# hurf1_board.net
KiCad netlist of a schematic drawn in EAGLE
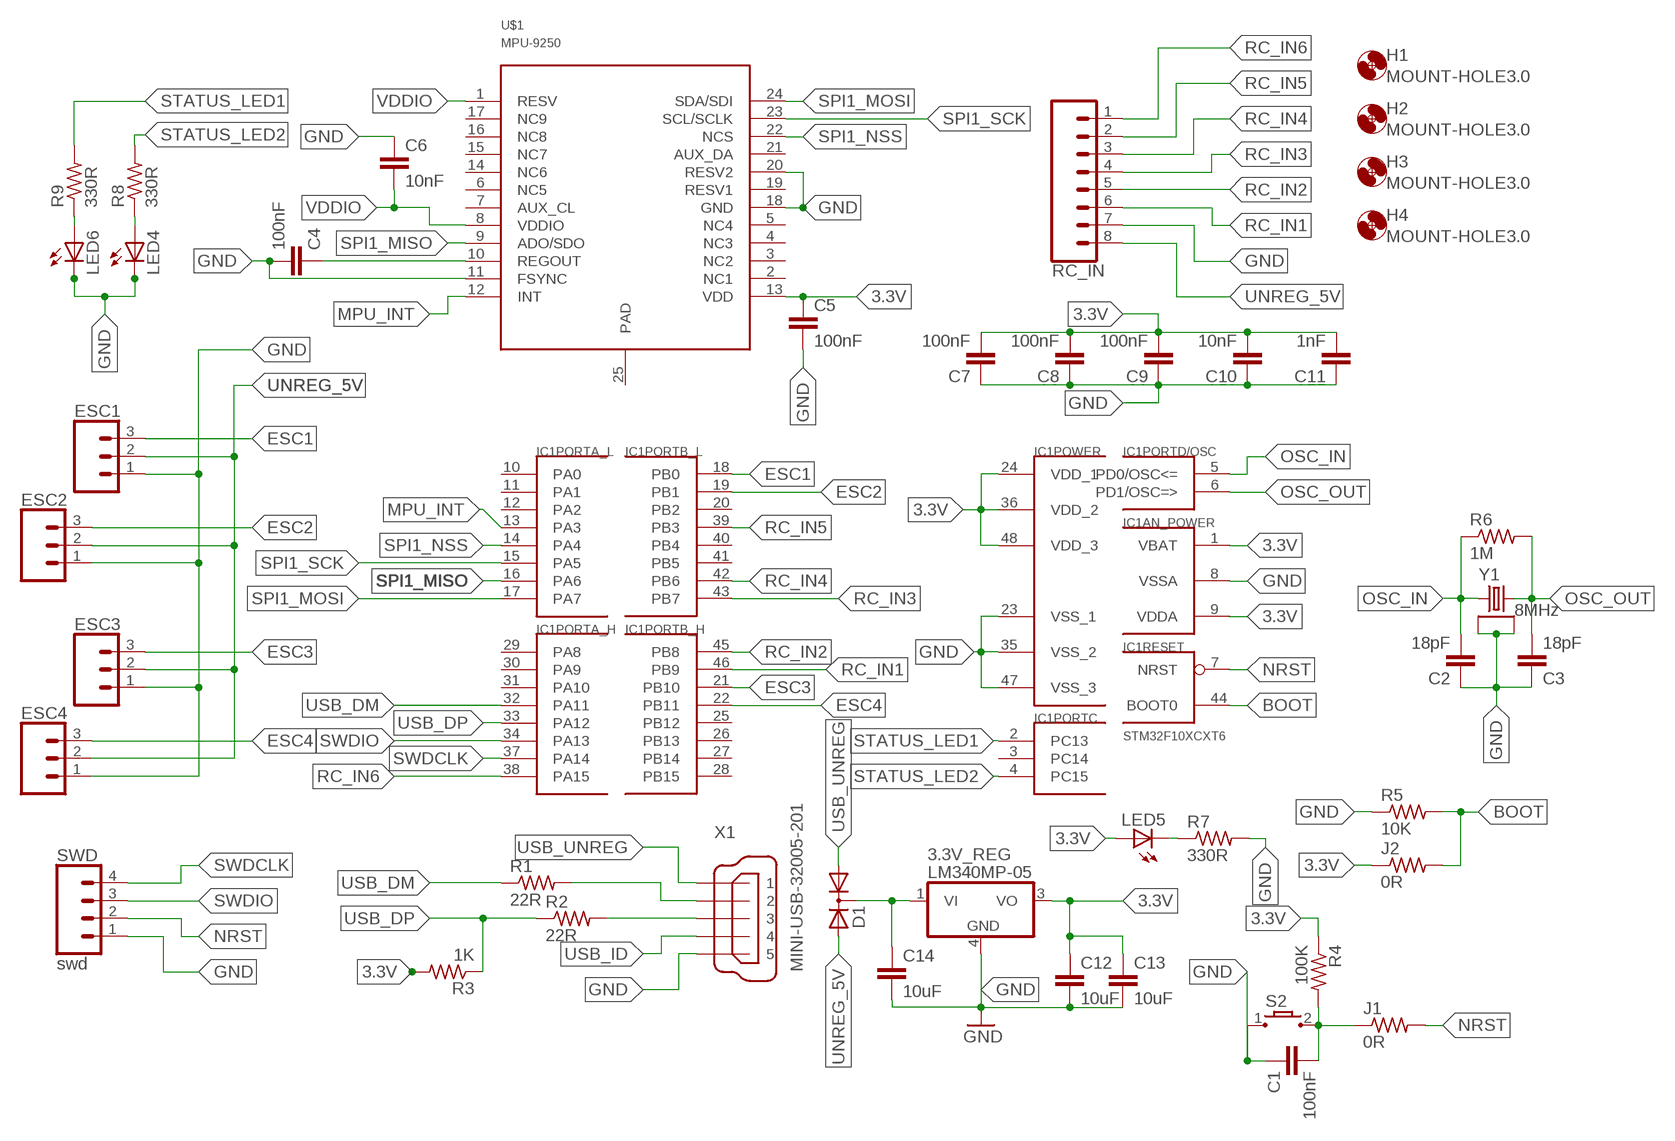
[diagram p0: schematic, sheet 1]

(export (version "E")
  (design (tool "Eeschema 10.0.6"))
  (components
    (comp (ref "3.3V_REG")
      (value "LM340MP-05")
      (footprint "eagle-import:SOT223")
      (libsource (lib "eagle-import") (part "LM340?-MP05"))
    )
    (comp (ref "C1")
      (value "100nF")
      (footprint "eagle-import:C0603")
      (libsource (lib "eagle-import") (part "C-EUC0603"))
    )
    (comp (ref "C2")
      (value "18pF")
      (footprint "eagle-import:C0603")
      (libsource (lib "eagle-import") (part "C-EUC0603"))
    )
    (comp (ref "C3")
      (value "18pF")
      (footprint "eagle-import:C0603")
      (libsource (lib "eagle-import") (part "C-EUC0603"))
    )
    (comp (ref "C4")
      (value "100nF")
      (footprint "eagle-import:C0805K")
      (libsource (lib "eagle-import") (part "resistor_348_C-EUC0805K"))
    )
    (comp (ref "C5")
      (value "100nF")
      (footprint "eagle-import:C0603")
      (libsource (lib "eagle-import") (part "C-EUC0603"))
    )
    (comp (ref "C6")
      (value "10nF")
      (footprint "eagle-import:C0603")
      (libsource (lib "eagle-import") (part "C-EUC0603"))
    )
    (comp (ref "C7")
      (value "100nF")
      (footprint "eagle-import:C0603")
      (libsource (lib "eagle-import") (part "C-EUC0603"))
    )
    (comp (ref "C8")
      (value "100nF")
      (footprint "eagle-import:C0603")
      (libsource (lib "eagle-import") (part "C-EUC0603"))
    )
    (comp (ref "C9")
      (value "100nF")
      (footprint "eagle-import:C0603")
      (libsource (lib "eagle-import") (part "C-EUC0603"))
    )
    (comp (ref "C10")
      (value "10nF")
      (footprint "eagle-import:C0603")
      (libsource (lib "eagle-import") (part "C-EUC0603"))
    )
    (comp (ref "C11")
      (value "1nF")
      (footprint "eagle-import:C0603")
      (libsource (lib "eagle-import") (part "C-EUC0603"))
    )
    (comp (ref "C12")
      (value "10uF")
      (footprint "eagle-import:C0805")
      (libsource (lib "eagle-import") (part "C-EUC0805"))
    )
    (comp (ref "C13")
      (value "10uF")
      (footprint "eagle-import:C0805")
      (libsource (lib "eagle-import") (part "C-EUC0805"))
    )
    (comp (ref "C14")
      (value "10uF")
      (footprint "eagle-import:C0805")
      (libsource (lib "eagle-import") (part "C-EUC0805"))
    )
    (comp (ref "D1")
      (value "DIODE-2AC|CASOT23")
      (footprint "eagle-import:SOT23")
      (libsource (lib "eagle-import") (part "DIODE-2AC|CASOT23"))
    )
    (comp (ref "ESC1")
      (value "CONN_03")
      (footprint "eagle-import:1X03")
      (libsource (lib "eagle-import") (part "CONN_03"))
    )
    (comp (ref "ESC2")
      (value "CONN_03")
      (footprint "eagle-import:1X03")
      (libsource (lib "eagle-import") (part "CONN_03"))
    )
    (comp (ref "ESC3")
      (value "CONN_03")
      (footprint "eagle-import:1X03")
      (libsource (lib "eagle-import") (part "CONN_03"))
    )
    (comp (ref "ESC4")
      (value "CONN_03")
      (footprint "eagle-import:1X03")
      (libsource (lib "eagle-import") (part "CONN_03"))
    )
    (comp (ref "H1")
      (value "MOUNT-HOLE3.0")
      (footprint "eagle-import:3,0")
      (libsource (lib "eagle-import") (part "MOUNT-HOLE3.0"))
    )
    (comp (ref "H2")
      (value "MOUNT-HOLE3.0")
      (footprint "eagle-import:3,0")
      (libsource (lib "eagle-import") (part "MOUNT-HOLE3.0"))
    )
    (comp (ref "H3")
      (value "MOUNT-HOLE3.0")
      (footprint "eagle-import:3,0")
      (libsource (lib "eagle-import") (part "MOUNT-HOLE3.0"))
    )
    (comp (ref "H4")
      (value "MOUNT-HOLE3.0")
      (footprint "eagle-import:3,0")
      (libsource (lib "eagle-import") (part "MOUNT-HOLE3.0"))
    )
    (comp (ref "IC1")
      (value "STM32F10XCXT6")
      (footprint "eagle-import:TQFP48")
      (libsource (lib "eagle-import") (part "STM32F10XCXT6"))
    )
    (comp (ref "J1")
      (value "0R")
      (footprint "eagle-import:R0603")
      (libsource (lib "eagle-import") (part "R-US_R0603"))
    )
    (comp (ref "J2")
      (value "0R")
      (footprint "eagle-import:R0603")
      (libsource (lib "eagle-import") (part "R-US_R0603"))
    )
    (comp (ref "LED4")
      (value "LEDSML0805")
      (footprint "eagle-import:SML0805")
      (libsource (lib "eagle-import") (part "LEDSML0805"))
    )
    (comp (ref "LED5")
      (value "LEDSML0805")
      (footprint "eagle-import:SML0805")
      (libsource (lib "eagle-import") (part "LEDSML0805"))
    )
    (comp (ref "LED6")
      (value "LEDSML0805")
      (footprint "eagle-import:SML0805")
      (libsource (lib "eagle-import") (part "LEDSML0805"))
    )
    (comp (ref "R1")
      (value "22R")
      (footprint "eagle-import:R0603")
      (libsource (lib "eagle-import") (part "R-US_R0603"))
    )
    (comp (ref "R2")
      (value "22R")
      (footprint "eagle-import:R0603")
      (libsource (lib "eagle-import") (part "R-US_R0603"))
    )
    (comp (ref "R3")
      (value "1K")
      (footprint "eagle-import:R0603")
      (libsource (lib "eagle-import") (part "R-US_R0603"))
    )
    (comp (ref "R4")
      (value "100K")
      (footprint "eagle-import:R0603")
      (libsource (lib "eagle-import") (part "R-US_R0603"))
    )
    (comp (ref "R5")
      (value "10K")
      (footprint "eagle-import:R0603")
      (libsource (lib "eagle-import") (part "R-US_R0603"))
    )
    (comp (ref "R6")
      (value "1M")
      (footprint "eagle-import:R0603")
      (libsource (lib "eagle-import") (part "R-US_R0603"))
    )
    (comp (ref "R7")
      (value "330R")
      (footprint "eagle-import:R0603")
      (libsource (lib "eagle-import") (part "R-US_R0603"))
    )
    (comp (ref "R8")
      (value "330R")
      (footprint "eagle-import:R0603")
      (libsource (lib "eagle-import") (part "R-US_R0603"))
    )
    (comp (ref "R9")
      (value "330R")
      (footprint "eagle-import:R0603")
      (libsource (lib "eagle-import") (part "R-US_R0603"))
    )
    (comp (ref "RC_IN")
      (value "CONN_08")
      (footprint "eagle-import:1X08_1MM_RA")
      (libsource (lib "eagle-import") (part "CONN_08"))
    )
    (comp (ref "S2")
      (value "TL3302-G")
      (footprint "eagle-import:TL3302_GULL_WING")
      (libsource (lib "eagle-import") (part "TL3302-G"))
    )
    (comp (ref "SWD")
      (value "swd")
      (footprint "eagle-import:1X04_1MM_RA")
      (libsource (lib "eagle-import") (part "CONN_04SMD2"))
    )
    (comp (ref "U$1")
      (value "MPU-9250")
      (footprint "eagle-import:LEAD-QFN24")
      (libsource (lib "eagle-import") (part "MPU-9250"))
    )
    (comp (ref "X1")
      (value "MINI-USB-32005-201")
      (footprint "eagle-import:32005-201")
      (libsource (lib "eagle-import") (part "MINI-USB-32005-201"))
    )
    (comp (ref "Y1")
      (value "8MHz")
      (footprint "eagle-import:GSX-531")
      (libsource (lib "eagle-import") (part "GSX-531"))
    )
  )
  (nets
    (net (code "1") (name "3.3V") (class "Default")
      (node (ref "3.3V_REG") (pin "3") (pinfunction "VO_3") (pintype "passive"))
      (node (ref "C10") (pin "2") (pinfunction "2_2") (pintype "passive"))
      (node (ref "C11") (pin "2") (pinfunction "2_2") (pintype "passive"))
      (node (ref "C12") (pin "1") (pinfunction "1_1") (pintype "passive"))
      (node (ref "C13") (pin "1") (pinfunction "1_1") (pintype "passive"))
      (node (ref "C5") (pin "1") (pinfunction "1_1") (pintype "passive"))
      (node (ref "C7") (pin "2") (pinfunction "2_2") (pintype "passive"))
      (node (ref "C8") (pin "2") (pinfunction "2_2") (pintype "passive"))
      (node (ref "C9") (pin "2") (pinfunction "2_2") (pintype "passive"))
      (node (ref "IC1") (pin "1") (pinfunction "VBAT_1") (pintype "power_in"))
      (node (ref "IC1") (pin "24") (pinfunction "VDD_1_24") (pintype "power_in"))
      (node (ref "IC1") (pin "36") (pinfunction "VDD_2_36") (pintype "power_in"))
      (node (ref "IC1") (pin "48") (pinfunction "VDD_3_48") (pintype "power_in"))
      (node (ref "IC1") (pin "9") (pinfunction "VDDA_9") (pintype "power_in"))
      (node (ref "J2") (pin "1") (pinfunction "1_1") (pintype "passive"))
      (node (ref "LED5") (pin "A") (pinfunction "A_A") (pintype "passive"))
      (node (ref "R3") (pin "2") (pinfunction "2_2") (pintype "passive"))
      (node (ref "R4") (pin "1") (pinfunction "1_1") (pintype "passive"))
      (node (ref "U$1") (pin "13") (pinfunction "VDD_13") (pintype "bidirectional"))
    )
    (net (code "2") (name "BOOT") (class "Default")
      (node (ref "IC1") (pin "44") (pinfunction "BOOT0_44") (pintype "input"))
      (node (ref "J2") (pin "2") (pinfunction "2_2") (pintype "passive"))
      (node (ref "R5") (pin "2") (pinfunction "2_2") (pintype "passive"))
    )
    (net (code "3") (name "ESC1") (class "Default")
      (node (ref "ESC1") (pin "3") (pinfunction "3_3") (pintype "passive"))
      (node (ref "IC1") (pin "18") (pinfunction "PB0_18") (pintype "bidirectional"))
    )
    (net (code "4") (name "ESC2") (class "Default")
      (node (ref "ESC2") (pin "3") (pinfunction "3_3") (pintype "passive"))
      (node (ref "IC1") (pin "19") (pinfunction "PB1_19") (pintype "bidirectional"))
    )
    (net (code "5") (name "ESC3") (class "Default")
      (node (ref "ESC3") (pin "3") (pinfunction "3_3") (pintype "passive"))
      (node (ref "IC1") (pin "21") (pinfunction "PB10_21") (pintype "bidirectional"))
    )
    (net (code "6") (name "ESC4") (class "Default")
      (node (ref "ESC4") (pin "3") (pinfunction "3_3") (pintype "passive"))
      (node (ref "IC1") (pin "22") (pinfunction "PB11_22") (pintype "bidirectional"))
    )
    (net (code "7") (name "GND") (class "Default")
      (node (ref "3.3V_REG") (pin "4") (pinfunction "GND_4") (pintype "passive"))
      (node (ref "C1") (pin "1") (pinfunction "1_1") (pintype "passive"))
      (node (ref "C10") (pin "1") (pinfunction "1_1") (pintype "passive"))
      (node (ref "C11") (pin "1") (pinfunction "1_1") (pintype "passive"))
      (node (ref "C12") (pin "2") (pinfunction "2_2") (pintype "passive"))
      (node (ref "C13") (pin "2") (pinfunction "2_2") (pintype "passive"))
      (node (ref "C14") (pin "2") (pinfunction "2_2") (pintype "passive"))
      (node (ref "C2") (pin "1") (pinfunction "1_1") (pintype "passive"))
      (node (ref "C3") (pin "1") (pinfunction "1_1") (pintype "passive"))
      (node (ref "C4") (pin "2") (pinfunction "2_2") (pintype "passive"))
      (node (ref "C5") (pin "2") (pinfunction "2_2") (pintype "passive"))
      (node (ref "C6") (pin "1") (pinfunction "1_1") (pintype "passive"))
      (node (ref "C7") (pin "1") (pinfunction "1_1") (pintype "passive"))
      (node (ref "C8") (pin "1") (pinfunction "1_1") (pintype "passive"))
      (node (ref "C9") (pin "1") (pinfunction "1_1") (pintype "passive"))
      (node (ref "ESC1") (pin "1") (pinfunction "1_1") (pintype "passive"))
      (node (ref "ESC2") (pin "1") (pinfunction "1_1") (pintype "passive"))
      (node (ref "ESC3") (pin "1") (pinfunction "1_1") (pintype "passive"))
      (node (ref "ESC4") (pin "1") (pinfunction "1_1") (pintype "passive"))
      (node (ref "IC1") (pin "23") (pinfunction "VSS_1_23") (pintype "power_in"))
      (node (ref "IC1") (pin "35") (pinfunction "VSS_2_35") (pintype "power_in"))
      (node (ref "IC1") (pin "47") (pinfunction "VSS_3_47") (pintype "power_in"))
      (node (ref "IC1") (pin "8") (pinfunction "VSSA_8") (pintype "power_in"))
      (node (ref "LED4") (pin "C") (pinfunction "C_C") (pintype "passive"))
      (node (ref "LED6") (pin "C") (pinfunction "C_C") (pintype "passive"))
      (node (ref "R5") (pin "1") (pinfunction "1_1") (pintype "passive"))
      (node (ref "R7") (pin "2") (pinfunction "2_2") (pintype "passive"))
      (node (ref "RC_IN") (pin "7") (pinfunction "7_7") (pintype "passive"))
      (node (ref "S2") (pin "1") (pinfunction "1_1") (pintype "passive"))
      (node (ref "SWD") (pin "1") (pinfunction "1_1") (pintype "passive"))
      (node (ref "U$1") (pin "11") (pinfunction "FSYNC_11") (pintype "bidirectional"))
      (node (ref "U$1") (pin "18") (pinfunction "GND_18") (pintype "bidirectional"))
      (node (ref "U$1") (pin "20") (pinfunction "RESV2_20") (pintype "bidirectional"))
      (node (ref "X1") (pin "5") (pinfunction "5_5") (pintype "passive"))
      (node (ref "Y1") (pin "2") (pinfunction "2_2") (pintype "passive"))
      (node (ref "Y1") (pin "4") (pinfunction "4_4") (pintype "passive"))
    )
    (net (code "8") (name "MPU_INT") (class "Default")
      (node (ref "IC1") (pin "13") (pinfunction "PA3_13") (pintype "bidirectional"))
      (node (ref "U$1") (pin "12") (pinfunction "INT_12") (pintype "bidirectional"))
    )
    (net (code "9") (name "NRST") (class "Default")
      (node (ref "IC1") (pin "7") (pinfunction "NRST_7") (pintype "input"))
      (node (ref "J1") (pin "2") (pinfunction "2_2") (pintype "passive"))
      (node (ref "SWD") (pin "2") (pinfunction "2_2") (pintype "passive"))
    )
    (net (code "10") (name "Net-(3.3V_REG-VI)") (class "Default")
      (node (ref "3.3V_REG") (pin "1") (pinfunction "VI_1") (pintype "input"))
      (node (ref "C14") (pin "1") (pinfunction "1_1") (pintype "passive"))
      (node (ref "D1") (pin "3") (pinfunction "C_3") (pintype "passive"))
    )
    (net (code "11") (name "Net-(C1-Pad2)") (class "Default")
      (node (ref "C1") (pin "2") (pinfunction "2_2") (pintype "passive"))
      (node (ref "J1") (pin "1") (pinfunction "1_1") (pintype "passive"))
      (node (ref "R4") (pin "2") (pinfunction "2_2") (pintype "passive"))
      (node (ref "S2") (pin "2") (pinfunction "2_2") (pintype "passive"))
    )
    (net (code "12") (name "Net-(LED4-PadA)") (class "Default")
      (node (ref "LED4") (pin "A") (pinfunction "A_A") (pintype "passive"))
      (node (ref "R8") (pin "1") (pinfunction "1_1") (pintype "passive"))
    )
    (net (code "13") (name "Net-(LED5-PadC)") (class "Default")
      (node (ref "LED5") (pin "C") (pinfunction "C_C") (pintype "passive"))
      (node (ref "R7") (pin "1") (pinfunction "1_1") (pintype "passive"))
    )
    (net (code "14") (name "Net-(LED6-PadA)") (class "Default")
      (node (ref "LED6") (pin "A") (pinfunction "A_A") (pintype "passive"))
      (node (ref "R9") (pin "1") (pinfunction "1_1") (pintype "passive"))
    )
    (net (code "15") (name "Net-(R1-Pad2)") (class "Default")
      (node (ref "R1") (pin "2") (pinfunction "2_2") (pintype "passive"))
      (node (ref "X1") (pin "2") (pinfunction "2_2") (pintype "passive"))
    )
    (net (code "16") (name "Net-(R2-Pad2)") (class "Default")
      (node (ref "R2") (pin "2") (pinfunction "2_2") (pintype "passive"))
      (node (ref "X1") (pin "3") (pinfunction "3_3") (pintype "passive"))
    )
    (net (code "17") (name "Net-(U$1-REGOUT)") (class "Default")
      (node (ref "C4") (pin "1") (pinfunction "1_1") (pintype "passive"))
      (node (ref "U$1") (pin "10") (pinfunction "REGOUT_10") (pintype "bidirectional"))
    )
    (net (code "18") (name "OSC_IN") (class "Default")
      (node (ref "C2") (pin "2") (pinfunction "2_2") (pintype "passive"))
      (node (ref "IC1") (pin "5") (pinfunction "PD0/OSC<=_5") (pintype "bidirectional"))
      (node (ref "R6") (pin "1") (pinfunction "1_1") (pintype "passive"))
      (node (ref "Y1") (pin "1") (pinfunction "1_1") (pintype "passive"))
    )
    (net (code "19") (name "OSC_OUT") (class "Default")
      (node (ref "C3") (pin "2") (pinfunction "2_2") (pintype "passive"))
      (node (ref "IC1") (pin "6") (pinfunction "PD1/OSC=>_6") (pintype "bidirectional"))
      (node (ref "R6") (pin "2") (pinfunction "2_2") (pintype "passive"))
      (node (ref "Y1") (pin "3") (pinfunction "3_3") (pintype "passive"))
    )
    (net (code "20") (name "RC_IN1") (class "Default")
      (node (ref "IC1") (pin "46") (pinfunction "PB9_46") (pintype "bidirectional"))
      (node (ref "RC_IN") (pin "6") (pinfunction "6_6") (pintype "passive"))
    )
    (net (code "21") (name "RC_IN2") (class "Default")
      (node (ref "IC1") (pin "45") (pinfunction "PB8_45") (pintype "bidirectional"))
      (node (ref "RC_IN") (pin "5") (pinfunction "5_5") (pintype "passive"))
    )
    (net (code "22") (name "RC_IN3") (class "Default")
      (node (ref "IC1") (pin "43") (pinfunction "PB7_43") (pintype "bidirectional"))
      (node (ref "RC_IN") (pin "4") (pinfunction "4_4") (pintype "passive"))
    )
    (net (code "23") (name "RC_IN4") (class "Default")
      (node (ref "IC1") (pin "42") (pinfunction "PB6_42") (pintype "bidirectional"))
      (node (ref "RC_IN") (pin "3") (pinfunction "3_3") (pintype "passive"))
    )
    (net (code "24") (name "RC_IN5") (class "Default")
      (node (ref "IC1") (pin "39") (pinfunction "PB3_39") (pintype "bidirectional"))
      (node (ref "RC_IN") (pin "2") (pinfunction "2_2") (pintype "passive"))
    )
    (net (code "25") (name "RC_IN6") (class "Default")
      (node (ref "IC1") (pin "38") (pinfunction "PA15_38") (pintype "bidirectional"))
      (node (ref "RC_IN") (pin "1") (pinfunction "1_1") (pintype "passive"))
    )
    (net (code "26") (name "SPI1_MISO") (class "Default")
      (node (ref "IC1") (pin "16") (pinfunction "PA6_16") (pintype "bidirectional"))
      (node (ref "U$1") (pin "9") (pinfunction "ADO/SDO_9") (pintype "bidirectional"))
    )
    (net (code "27") (name "SPI1_MOSI") (class "Default")
      (node (ref "IC1") (pin "17") (pinfunction "PA7_17") (pintype "bidirectional"))
      (node (ref "U$1") (pin "24") (pinfunction "SDA/SDI_24") (pintype "bidirectional"))
    )
    (net (code "28") (name "SPI1_NSS") (class "Default")
      (node (ref "IC1") (pin "14") (pinfunction "PA4_14") (pintype "bidirectional"))
      (node (ref "U$1") (pin "22") (pinfunction "NCS_22") (pintype "bidirectional"))
    )
    (net (code "29") (name "SPI1_SCK") (class "Default")
      (node (ref "IC1") (pin "15") (pinfunction "PA5_15") (pintype "bidirectional"))
      (node (ref "U$1") (pin "23") (pinfunction "SCL/SCLK_23") (pintype "bidirectional"))
    )
    (net (code "30") (name "STATUS_LED1") (class "Default")
      (node (ref "IC1") (pin "2") (pinfunction "PC13_2") (pintype "bidirectional"))
      (node (ref "R9") (pin "2") (pinfunction "2_2") (pintype "passive"))
    )
    (net (code "31") (name "STATUS_LED2") (class "Default")
      (node (ref "IC1") (pin "4") (pinfunction "PC15_4") (pintype "bidirectional"))
      (node (ref "R8") (pin "2") (pinfunction "2_2") (pintype "passive"))
    )
    (net (code "32") (name "SWDCLK") (class "Default")
      (node (ref "IC1") (pin "37") (pinfunction "PA14_37") (pintype "bidirectional"))
      (node (ref "SWD") (pin "4") (pinfunction "4_4") (pintype "passive"))
    )
    (net (code "33") (name "SWDIO") (class "Default")
      (node (ref "IC1") (pin "34") (pinfunction "PA13_34") (pintype "bidirectional"))
      (node (ref "SWD") (pin "3") (pinfunction "3_3") (pintype "passive"))
    )
    (net (code "34") (name "UNREG_5V") (class "Default")
      (node (ref "D1") (pin "2") (pinfunction "A2_2") (pintype "passive"))
      (node (ref "ESC1") (pin "2") (pinfunction "2_2") (pintype "passive"))
      (node (ref "ESC2") (pin "2") (pinfunction "2_2") (pintype "passive"))
      (node (ref "ESC3") (pin "2") (pinfunction "2_2") (pintype "passive"))
      (node (ref "ESC4") (pin "2") (pinfunction "2_2") (pintype "passive"))
      (node (ref "RC_IN") (pin "8") (pinfunction "8_8") (pintype "passive"))
    )
    (net (code "35") (name "USB_DM") (class "Default")
      (node (ref "IC1") (pin "32") (pinfunction "PA11_32") (pintype "bidirectional"))
      (node (ref "R1") (pin "1") (pinfunction "1_1") (pintype "passive"))
    )
    (net (code "36") (name "USB_DP") (class "Default")
      (node (ref "IC1") (pin "33") (pinfunction "PA12_33") (pintype "bidirectional"))
      (node (ref "R2") (pin "1") (pinfunction "1_1") (pintype "passive"))
      (node (ref "R3") (pin "1") (pinfunction "1_1") (pintype "passive"))
    )
    (net (code "37") (name "USB_ID") (class "Default")
      (node (ref "X1") (pin "4") (pinfunction "4_4") (pintype "passive"))
    )
    (net (code "38") (name "USB_UNREG") (class "Default")
      (node (ref "D1") (pin "1") (pinfunction "A1_1") (pintype "passive"))
      (node (ref "X1") (pin "1") (pinfunction "1_1") (pintype "passive"))
    )
    (net (code "39") (name "VDDIO") (class "Default")
      (node (ref "C6") (pin "2") (pinfunction "2_2") (pintype "passive"))
      (node (ref "U$1") (pin "1") (pinfunction "RESV_1") (pintype "bidirectional"))
      (node (ref "U$1") (pin "8") (pinfunction "VDDIO_8") (pintype "bidirectional"))
    )
    (net (code "40") (name "unconnected-(IC1B-PA8-Pad29)") (class "Default")
      (node (ref "IC1") (pin "29") (pinfunction "PA8_29") (pintype "bidirectional"))
    )
    (net (code "41") (name "unconnected-(IC1B-PA9-Pad30)") (class "Default")
      (node (ref "IC1") (pin "30") (pinfunction "PA9_30") (pintype "bidirectional"))
    )
    (net (code "42") (name "unconnected-(IC1B-PA10-Pad31)") (class "Default")
      (node (ref "IC1") (pin "31") (pinfunction "PA10_31") (pintype "bidirectional"))
    )
    (net (code "43") (name "unconnected-(IC1C-PA0-Pad10)") (class "Default")
      (node (ref "IC1") (pin "10") (pinfunction "PA0_10") (pintype "bidirectional"))
    )
    (net (code "44") (name "unconnected-(IC1C-PA1-Pad11)") (class "Default")
      (node (ref "IC1") (pin "11") (pinfunction "PA1_11") (pintype "bidirectional"))
    )
    (net (code "45") (name "unconnected-(IC1C-PA2-Pad12)") (class "Default")
      (node (ref "IC1") (pin "12") (pinfunction "PA2_12") (pintype "bidirectional"))
    )
    (net (code "46") (name "unconnected-(IC1D-PB12-Pad25)") (class "Default")
      (node (ref "IC1") (pin "25") (pinfunction "PB12_25") (pintype "bidirectional"))
    )
    (net (code "47") (name "unconnected-(IC1D-PB13-Pad26)") (class "Default")
      (node (ref "IC1") (pin "26") (pinfunction "PB13_26") (pintype "bidirectional"))
    )
    (net (code "48") (name "unconnected-(IC1D-PB14-Pad27)") (class "Default")
      (node (ref "IC1") (pin "27") (pinfunction "PB14_27") (pintype "bidirectional"))
    )
    (net (code "49") (name "unconnected-(IC1D-PB15-Pad28)") (class "Default")
      (node (ref "IC1") (pin "28") (pinfunction "PB15_28") (pintype "bidirectional"))
    )
    (net (code "50") (name "unconnected-(IC1E-PB2-Pad20)") (class "Default")
      (node (ref "IC1") (pin "20") (pinfunction "PB2_20") (pintype "bidirectional"))
    )
    (net (code "51") (name "unconnected-(IC1E-PB4-Pad40)") (class "Default")
      (node (ref "IC1") (pin "40") (pinfunction "PB4_40") (pintype "bidirectional"))
    )
    (net (code "52") (name "unconnected-(IC1E-PB5-Pad41)") (class "Default")
      (node (ref "IC1") (pin "41") (pinfunction "PB5_41") (pintype "bidirectional"))
    )
    (net (code "53") (name "unconnected-(IC1F-PC14-Pad3)") (class "Default")
      (node (ref "IC1") (pin "3") (pinfunction "PC14_3") (pintype "bidirectional"))
    )
    (net (code "54") (name "unconnected-(U$1-AUX_CL-Pad7)") (class "Default")
      (node (ref "U$1") (pin "7") (pinfunction "AUX_CL_7") (pintype "bidirectional"))
    )
    (net (code "55") (name "unconnected-(U$1-AUX_DA-Pad21)") (class "Default")
      (node (ref "U$1") (pin "21") (pinfunction "AUX_DA_21") (pintype "bidirectional"))
    )
    (net (code "56") (name "unconnected-(U$1-NC1-Pad2)") (class "Default")
      (node (ref "U$1") (pin "2") (pinfunction "NC1_2") (pintype "bidirectional"))
    )
    (net (code "57") (name "unconnected-(U$1-NC2-Pad3)") (class "Default")
      (node (ref "U$1") (pin "3") (pinfunction "NC2_3") (pintype "bidirectional"))
    )
    (net (code "58") (name "unconnected-(U$1-NC3-Pad4)") (class "Default")
      (node (ref "U$1") (pin "4") (pinfunction "NC3_4") (pintype "bidirectional"))
    )
    (net (code "59") (name "unconnected-(U$1-NC4-Pad5)") (class "Default")
      (node (ref "U$1") (pin "5") (pinfunction "NC4_5") (pintype "bidirectional"))
    )
    (net (code "60") (name "unconnected-(U$1-NC5-Pad6)") (class "Default")
      (node (ref "U$1") (pin "6") (pinfunction "NC5_6") (pintype "bidirectional"))
    )
    (net (code "61") (name "unconnected-(U$1-NC6-Pad14)") (class "Default")
      (node (ref "U$1") (pin "14") (pinfunction "NC6_14") (pintype "bidirectional"))
    )
    (net (code "62") (name "unconnected-(U$1-NC7-Pad15)") (class "Default")
      (node (ref "U$1") (pin "15") (pinfunction "NC7_15") (pintype "bidirectional"))
    )
    (net (code "63") (name "unconnected-(U$1-NC8-Pad16)") (class "Default")
      (node (ref "U$1") (pin "16") (pinfunction "NC8_16") (pintype "bidirectional"))
    )
    (net (code "64") (name "unconnected-(U$1-NC9-Pad17)") (class "Default")
      (node (ref "U$1") (pin "17") (pinfunction "NC9_17") (pintype "bidirectional"))
    )
    (net (code "65") (name "unconnected-(U$1-PAD-Pad25)") (class "Default")
      (node (ref "U$1") (pin "25") (pinfunction "PAD_25") (pintype "bidirectional"))
    )
    (net (code "66") (name "unconnected-(U$1-RESV1-Pad19)") (class "Default")
      (node (ref "U$1") (pin "19") (pinfunction "RESV1_19") (pintype "bidirectional"))
    )
  )
)
